# ADE7753.net
KiCad netlist of a schematic drawn in Altium Designer
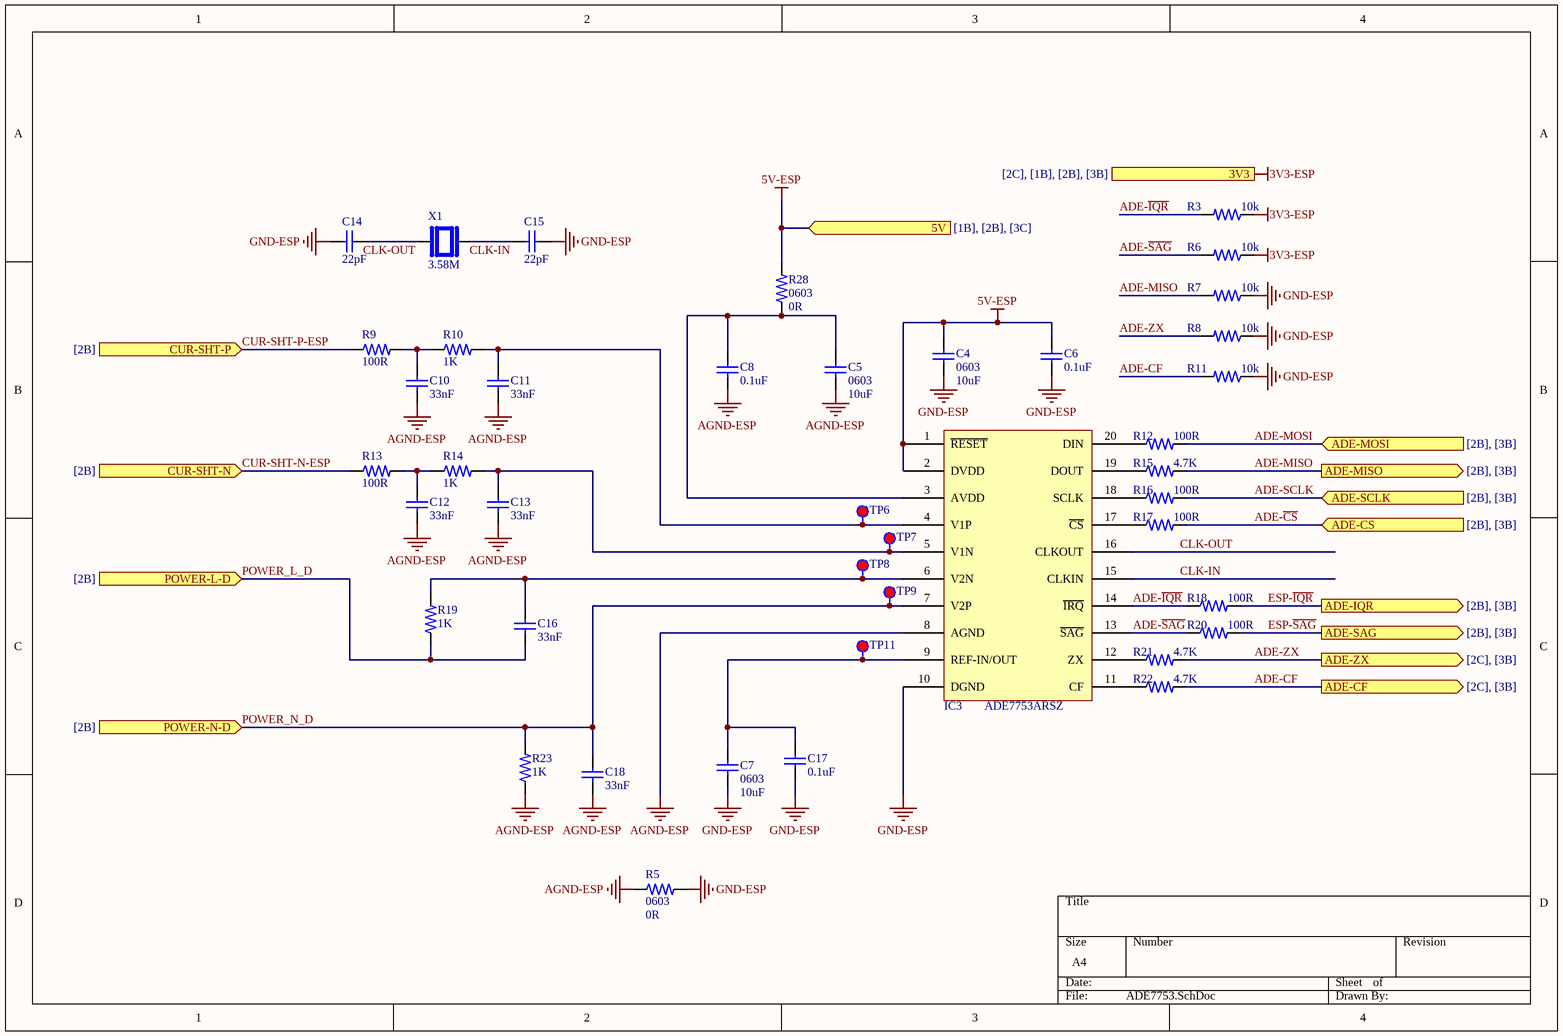
[diagram p0: ADE7753.SchDoc]

(export (version "E")
  (design (tool "Eeschema 10.0.6"))
  (components
    (comp (ref "C4")
      (value "10uF")
      (footprint "SMD-CAP-0603-YAGEO")
      (description "Multilayer Ceramic Capacitor, 10 uF, 25 V, ï¿½ 20%, X5R, 0603 [1608 Metric]")
      (fields
        (field (name "MANUFACTURER") "Yageo")
        (field (name "MANUFACTURER PART NUMBER") "CC0603MRX5R8BB106")
        (field (name "PACKAGE") "0603")
        (field (name "DESIGNER") "TVBac")
      )
      (libsource (lib "Capacitors") (part "CAP; 10uF; 25V; SMD; 0603; CC0603MRX5R8BB106"))
    )
    (comp (ref "C5")
      (value "10uF")
      (footprint "SMD-CAP-0603-YAGEO")
      (description "Multilayer Ceramic Capacitor, 10 uF, 25 V, ï¿½ 20%, X5R, 0603 [1608 Metric]")
      (fields
        (field (name "MANUFACTURER") "Yageo")
        (field (name "MANUFACTURER PART NUMBER") "CC0603MRX5R8BB106")
        (field (name "PACKAGE") "0603")
        (field (name "DESIGNER") "TVBac")
      )
      (libsource (lib "Capacitors") (part "CAP; 10uF; 25V; SMD; 0603; CC0603MRX5R8BB106"))
    )
    (comp (ref "C6")
      (value "0.1uF")
      (footprint "SMD-CAP-0603-YAGEO")
      (description "0603 0.1 uF 16 V ±10 % Tolerance X7R SMT Multilayer Ceramic Capacitor")
      (fields
        (field (name "MANUFACTURER") "Yageo")
        (field (name "MANUFACTURER PART NUMBER") "CC0603KRX7R7BB104")
        (field (name "DESIGNER") "TVBac")
      )
      (libsource (lib "Capacitors") (part "CAP; 0.1uF; 16V; 0603; SMD; CC0603KRX7R7BB104"))
    )
    (comp (ref "C7")
      (value "10uF")
      (footprint "SMD-CAP-0603-YAGEO")
      (description "Multilayer Ceramic Capacitor, 10 uF, 25 V, ï¿½ 20%, X5R, 0603 [1608 Metric]")
      (fields
        (field (name "MANUFACTURER") "Yageo")
        (field (name "MANUFACTURER PART NUMBER") "CC0603MRX5R8BB106")
        (field (name "PACKAGE") "0603")
        (field (name "DESIGNER") "TVBac")
      )
      (libsource (lib "Capacitors") (part "CAP; 10uF; 25V; SMD; 0603; CC0603MRX5R8BB106"))
    )
    (comp (ref "C8")
      (value "0.1uF")
      (footprint "SMD-CAP-0603-YAGEO")
      (description "0603 0.1 uF 16 V ±10 % Tolerance X7R SMT Multilayer Ceramic Capacitor")
      (fields
        (field (name "MANUFACTURER") "Yageo")
        (field (name "MANUFACTURER PART NUMBER") "CC0603KRX7R7BB104")
        (field (name "DESIGNER") "TVBac")
      )
      (libsource (lib "Capacitors") (part "CAP; 0.1uF; 16V; 0603; SMD; CC0603KRX7R7BB104"))
    )
    (comp (ref "C10")
      (value "33nF")
      (footprint "SMD-CAP-0603-KEMET")
      (description "Multilayer Ceramic Capacitors MLCC - SMD/SMT 16V 0.033uF X7R 0603 5%")
      (fields
        (field (name "MANUFACTURER") "KEMET")
        (field (name "MANUFACTURER PART NUMBER") "C0603C333J4REC7411")
        (field (name "DESIGNER") "TVBac")
      )
      (libsource (lib "Capacitors") (part "CAP; 0.033uF; 33nF; 0603; 16V; C0603C333J4REC7411"))
    )
    (comp (ref "C11")
      (value "33nF")
      (footprint "SMD-CAP-0603-KEMET")
      (description "Multilayer Ceramic Capacitors MLCC - SMD/SMT 16V 0.033uF X7R 0603 5%")
      (fields
        (field (name "MANUFACTURER") "KEMET")
        (field (name "MANUFACTURER PART NUMBER") "C0603C333J4REC7411")
        (field (name "DESIGNER") "TVBac")
      )
      (libsource (lib "Capacitors") (part "CAP; 0.033uF; 33nF; 0603; 16V; C0603C333J4REC7411"))
    )
    (comp (ref "C12")
      (value "33nF")
      (footprint "SMD-CAP-0603-KEMET")
      (description "Multilayer Ceramic Capacitors MLCC - SMD/SMT 16V 0.033uF X7R 0603 5%")
      (fields
        (field (name "MANUFACTURER") "KEMET")
        (field (name "MANUFACTURER PART NUMBER") "C0603C333J4REC7411")
        (field (name "DESIGNER") "TVBac")
      )
      (libsource (lib "Capacitors") (part "CAP; 0.033uF; 33nF; 0603; 16V; C0603C333J4REC7411"))
    )
    (comp (ref "C13")
      (value "33nF")
      (footprint "SMD-CAP-0603-KEMET")
      (description "Multilayer Ceramic Capacitors MLCC - SMD/SMT 16V 0.033uF X7R 0603 5%")
      (fields
        (field (name "MANUFACTURER") "KEMET")
        (field (name "MANUFACTURER PART NUMBER") "C0603C333J4REC7411")
        (field (name "DESIGNER") "TVBac")
      )
      (libsource (lib "Capacitors") (part "CAP; 0.033uF; 33nF; 0603; 16V; C0603C333J4REC7411"))
    )
    (comp (ref "C14")
      (value "22pF")
      (footprint "SMD-CAP-0603-YAGEO")
      (description "Multilayer Ceramic Capacitor, 22 pF, 50 V, ï¿½ 1%, C0G (NP0), 0603 [1608 Metric]")
      (fields
        (field (name "MANUFACTURER") "Yageo")
        (field (name "MANUFACTURER PART NUMBER") "CC0603FRNPO9BN220")
        (field (name "DESIGNER") "TVBac")
      )
      (libsource (lib "Capacitors") (part "CAP; 22pF; 50V; SMD; CC0603FRNPO9BN220"))
    )
    (comp (ref "C15")
      (value "22pF")
      (footprint "SMD-CAP-0603-YAGEO")
      (description "Multilayer Ceramic Capacitor, 22 pF, 50 V, ï¿½ 1%, C0G (NP0), 0603 [1608 Metric]")
      (fields
        (field (name "MANUFACTURER") "Yageo")
        (field (name "MANUFACTURER PART NUMBER") "CC0603FRNPO9BN220")
        (field (name "DESIGNER") "TVBac")
      )
      (libsource (lib "Capacitors") (part "CAP; 22pF; 50V; SMD; CC0603FRNPO9BN220"))
    )
    (comp (ref "C16")
      (value "33nF")
      (footprint "SMD-CAP-0603-KEMET")
      (description "Multilayer Ceramic Capacitors MLCC - SMD/SMT 16V 0.033uF X7R 0603 5%")
      (fields
        (field (name "MANUFACTURER") "KEMET")
        (field (name "MANUFACTURER PART NUMBER") "C0603C333J4REC7411")
        (field (name "DESIGNER") "TVBac")
      )
      (libsource (lib "Capacitors") (part "CAP; 0.033uF; 33nF; 0603; 16V; C0603C333J4REC7411"))
    )
    (comp (ref "C17")
      (value "0.1uF")
      (footprint "SMD-CAP-0603-YAGEO")
      (description "0603 0.1 uF 16 V ±10 % Tolerance X7R SMT Multilayer Ceramic Capacitor")
      (fields
        (field (name "MANUFACTURER") "Yageo")
        (field (name "MANUFACTURER PART NUMBER") "CC0603KRX7R7BB104")
        (field (name "DESIGNER") "TVBac")
      )
      (libsource (lib "Capacitors") (part "CAP; 0.1uF; 16V; 0603; SMD; CC0603KRX7R7BB104"))
    )
    (comp (ref "C18")
      (value "33nF")
      (footprint "SMD-CAP-0603-KEMET")
      (description "Multilayer Ceramic Capacitors MLCC - SMD/SMT 16V 0.033uF X7R 0603 5%")
      (fields
        (field (name "MANUFACTURER") "KEMET")
        (field (name "MANUFACTURER PART NUMBER") "C0603C333J4REC7411")
        (field (name "DESIGNER") "TVBac")
      )
      (libsource (lib "Capacitors") (part "CAP; 0.033uF; 33nF; 0603; 16V; C0603C333J4REC7411"))
    )
    (comp (ref "IC3")
      (value "Single Phase Meter IC 20-SSOP")
      (footprint "SSOP-20-ADI")
      (description "Single Phase Multifunction Metering IC 20-Pin SSOP Tube")
      (fields
        (field (name "MANUFACTURER") "Analog Devices")
        (field (name "MANUFACTURER PART NUMBER") "ADE7753ARSZ")
        (field (name "DESIGNER") "TVBac")
      )
      (libsource (lib "IC") (part "ADE7753ARSZ"))
    )
    (comp (ref "R3")
      (value "10k")
      (footprint "SMD-RES-0603-SEI")
      (description "SMD Chip Resistor, 10 kOhm, ± 1%, 250 mW, 0603 [1608 Metric], Thick Film, Anti-Surge")
      (fields
        (field (name "MANUFACTURER") "Rohm")
        (field (name "MANUFACTURER PART NUMBER") "ESR03EZPF1002")
        (field (name "DESIGNER") "TVBac")
      )
      (libsource (lib "Resistors") (part "RES; 10K; 0603; SMD; ESR03EZPF1002"))
    )
    (comp (ref "R5")
      (value "0R")
      (footprint "SMD-RES-0603-SEI")
      (description "Res Thick 0603 0 Ohm Jumper 1/10W 100Ppm/ C Smd Rohs Compliant: Yes")
      (fields
        (field (name "MANUFACTURER") "Stackpole Electronics")
        (field (name "MANUFACTURER PART NUMBER") "RMCF0603ZT0R00")
        (field (name "PACKAGE") "0603")
        (field (name "DESIGNER") "TVBac")
      )
      (libsource (lib "Resistors") (part "RES; 0R; 0603; SMD;  RMCF0603ZT0R00"))
    )
    (comp (ref "R6")
      (value "10k")
      (footprint "SMD-RES-0603-SEI")
      (description "SMD Chip Resistor, 10 kOhm, ± 1%, 250 mW, 0603 [1608 Metric], Thick Film, Anti-Surge")
      (fields
        (field (name "MANUFACTURER") "Rohm")
        (field (name "MANUFACTURER PART NUMBER") "ESR03EZPF1002")
        (field (name "DESIGNER") "TVBac")
      )
      (libsource (lib "Resistors") (part "RES; 10K; 0603; SMD; ESR03EZPF1002"))
    )
    (comp (ref "R7")
      (value "10k")
      (footprint "SMD-RES-0603-SEI")
      (description "SMD Chip Resistor, 10 kOhm, ± 1%, 250 mW, 0603 [1608 Metric], Thick Film, Anti-Surge")
      (fields
        (field (name "MANUFACTURER") "Rohm")
        (field (name "MANUFACTURER PART NUMBER") "ESR03EZPF1002")
        (field (name "DESIGNER") "TVBac")
      )
      (libsource (lib "Resistors") (part "RES; 10K; 0603; SMD; ESR03EZPF1002"))
    )
    (comp (ref "R8")
      (value "10k")
      (footprint "SMD-RES-0603-SEI")
      (description "SMD Chip Resistor, 10 kOhm, ± 1%, 250 mW, 0603 [1608 Metric], Thick Film, Anti-Surge")
      (fields
        (field (name "MANUFACTURER") "Rohm")
        (field (name "MANUFACTURER PART NUMBER") "ESR03EZPF1002")
        (field (name "DESIGNER") "TVBac")
      )
      (libsource (lib "Resistors") (part "RES; 10K; 0603; SMD; ESR03EZPF1002"))
    )
    (comp (ref "R9")
      (value "100R")
      (footprint "SMD-RES-0603-RS")
      (description "Res Thick Film 0603 100 Ohm 1% 0.1W(1/10W) ±100ppm/C Pad SMD T/R Automotive AEC-Q200")
      (fields
        (field (name "MANUFACTURER") "Rohm")
        (field (name "MANUFACTURER PART NUMBER") "KTR03EZPF1000")
        (field (name "DESIGNER") "TVBac")
      )
      (libsource (lib "Resistors") (part "RES; 100R; 0603; SMD; KTR03EZPF1000"))
    )
    (comp (ref "R10")
      (value "1K")
      (footprint "SMD-RES-0603-SEI")
      (description "SMD Chip Resistor, 1 kOhm, ± 1%, 250 mW, 0603 [1608 Metric], Thick Film, Anti-Surge")
      (fields
        (field (name "MANUFACTURER") "Rohm")
        (field (name "MANUFACTURER PART NUMBER") "ESR03EZPF1001")
        (field (name "DESIGNER") "TVBac")
      )
      (libsource (lib "Resistors") (part "RES; 1K; 0603; SMD; ESR03EZPF1001"))
    )
    (comp (ref "R11")
      (value "10k")
      (footprint "SMD-RES-0603-SEI")
      (description "SMD Chip Resistor, 10 kOhm, ± 1%, 250 mW, 0603 [1608 Metric], Thick Film, Anti-Surge")
      (fields
        (field (name "MANUFACTURER") "Rohm")
        (field (name "MANUFACTURER PART NUMBER") "ESR03EZPF1002")
        (field (name "DESIGNER") "TVBac")
      )
      (libsource (lib "Resistors") (part "RES; 10K; 0603; SMD; ESR03EZPF1002"))
    )
    (comp (ref "R12")
      (value "100R")
      (footprint "SMD-RES-0603-RS")
      (description "Res Thick Film 0603 100 Ohm 1% 0.1W(1/10W) ±100ppm/C Pad SMD T/R Automotive AEC-Q200")
      (fields
        (field (name "MANUFACTURER") "Rohm")
        (field (name "MANUFACTURER PART NUMBER") "KTR03EZPF1000")
        (field (name "DESIGNER") "TVBac")
      )
      (libsource (lib "Resistors") (part "RES; 100R; 0603; SMD; KTR03EZPF1000"))
    )
    (comp (ref "R13")
      (value "100R")
      (footprint "SMD-RES-0603-RS")
      (description "Res Thick Film 0603 100 Ohm 1% 0.1W(1/10W) ±100ppm/C Pad SMD T/R Automotive AEC-Q200")
      (fields
        (field (name "MANUFACTURER") "Rohm")
        (field (name "MANUFACTURER PART NUMBER") "KTR03EZPF1000")
        (field (name "DESIGNER") "TVBac")
      )
      (libsource (lib "Resistors") (part "RES; 100R; 0603; SMD; KTR03EZPF1000"))
    )
    (comp (ref "R14")
      (value "1K")
      (footprint "SMD-RES-0603-SEI")
      (description "SMD Chip Resistor, 1 kOhm, ± 1%, 250 mW, 0603 [1608 Metric], Thick Film, Anti-Surge")
      (fields
        (field (name "MANUFACTURER") "Rohm")
        (field (name "MANUFACTURER PART NUMBER") "ESR03EZPF1001")
        (field (name "DESIGNER") "TVBac")
      )
      (libsource (lib "Resistors") (part "RES; 1K; 0603; SMD; ESR03EZPF1001"))
    )
    (comp (ref "R15")
      (value "4.7K")
      (footprint "SMD-RES-0603-RS")
      (description "Res Anti-Sulfured Thick Film 0603 4.7k Ohm 1% 1/10W ±100ppm/°C Molded Paper T/R")
      (fields
        (field (name "MANUFACTURER") "Rohm")
        (field (name "MANUFACTURER PART NUMBER") "SFR03EZPF4701")
        (field (name "DESIGNER") "TVBac")
      )
      (libsource (lib "Resistors") (part "RES; 4.7K; 0603; SMD; SFR03EZPF4701"))
    )
    (comp (ref "R16")
      (value "100R")
      (footprint "SMD-RES-0603-RS")
      (description "Res Thick Film 0603 100 Ohm 1% 0.1W(1/10W) ±100ppm/C Pad SMD T/R Automotive AEC-Q200")
      (fields
        (field (name "MANUFACTURER") "Rohm")
        (field (name "MANUFACTURER PART NUMBER") "KTR03EZPF1000")
        (field (name "DESIGNER") "TVBac")
      )
      (libsource (lib "Resistors") (part "RES; 100R; 0603; SMD; KTR03EZPF1000"))
    )
    (comp (ref "R17")
      (value "100R")
      (footprint "SMD-RES-0603-RS")
      (description "Res Thick Film 0603 100 Ohm 1% 0.1W(1/10W) ±100ppm/C Pad SMD T/R Automotive AEC-Q200")
      (fields
        (field (name "MANUFACTURER") "Rohm")
        (field (name "MANUFACTURER PART NUMBER") "KTR03EZPF1000")
        (field (name "DESIGNER") "TVBac")
      )
      (libsource (lib "Resistors") (part "RES; 100R; 0603; SMD; KTR03EZPF1000"))
    )
    (comp (ref "R18")
      (value "100R")
      (footprint "SMD-RES-0603-RS")
      (description "Res Thick Film 0603 100 Ohm 1% 0.1W(1/10W) ±100ppm/C Pad SMD T/R Automotive AEC-Q200")
      (fields
        (field (name "MANUFACTURER") "Rohm")
        (field (name "MANUFACTURER PART NUMBER") "KTR03EZPF1000")
        (field (name "DESIGNER") "TVBac")
      )
      (libsource (lib "Resistors") (part "RES; 100R; 0603; SMD; KTR03EZPF1000"))
    )
    (comp (ref "R19")
      (value "1K")
      (footprint "SMD-RES-0603-SEI")
      (description "SMD Chip Resistor, 1 kOhm, ± 1%, 250 mW, 0603 [1608 Metric], Thick Film, Anti-Surge")
      (fields
        (field (name "MANUFACTURER") "Rohm")
        (field (name "MANUFACTURER PART NUMBER") "ESR03EZPF1001")
        (field (name "DESIGNER") "TVBac")
      )
      (libsource (lib "Resistors") (part "RES; 1K; 0603; SMD; ESR03EZPF1001"))
    )
    (comp (ref "R20")
      (value "100R")
      (footprint "SMD-RES-0603-RS")
      (description "Res Thick Film 0603 100 Ohm 1% 0.1W(1/10W) ±100ppm/C Pad SMD T/R Automotive AEC-Q200")
      (fields
        (field (name "MANUFACTURER") "Rohm")
        (field (name "MANUFACTURER PART NUMBER") "KTR03EZPF1000")
        (field (name "DESIGNER") "TVBac")
      )
      (libsource (lib "Resistors") (part "RES; 100R; 0603; SMD; KTR03EZPF1000"))
    )
    (comp (ref "R21")
      (value "4.7K")
      (footprint "SMD-RES-0603-RS")
      (description "Res Anti-Sulfured Thick Film 0603 4.7k Ohm 1% 1/10W ±100ppm/°C Molded Paper T/R")
      (fields
        (field (name "MANUFACTURER") "Rohm")
        (field (name "MANUFACTURER PART NUMBER") "SFR03EZPF4701")
        (field (name "DESIGNER") "TVBac")
      )
      (libsource (lib "Resistors") (part "RES; 4.7K; 0603; SMD; SFR03EZPF4701"))
    )
    (comp (ref "R22")
      (value "4.7K")
      (footprint "SMD-RES-0603-RS")
      (description "Res Anti-Sulfured Thick Film 0603 4.7k Ohm 1% 1/10W ±100ppm/°C Molded Paper T/R")
      (fields
        (field (name "MANUFACTURER") "Rohm")
        (field (name "MANUFACTURER PART NUMBER") "SFR03EZPF4701")
        (field (name "DESIGNER") "TVBac")
      )
      (libsource (lib "Resistors") (part "RES; 4.7K; 0603; SMD; SFR03EZPF4701"))
    )
    (comp (ref "R23")
      (value "1K")
      (footprint "SMD-RES-0603-SEI")
      (description "SMD Chip Resistor, 1 kOhm, ± 1%, 250 mW, 0603 [1608 Metric], Thick Film, Anti-Surge")
      (fields
        (field (name "MANUFACTURER") "Rohm")
        (field (name "MANUFACTURER PART NUMBER") "ESR03EZPF1001")
        (field (name "DESIGNER") "TVBac")
      )
      (libsource (lib "Resistors") (part "RES; 1K; 0603; SMD; ESR03EZPF1001"))
    )
    (comp (ref "R28")
      (value "0R")
      (footprint "SMD-RES-0603-SEI")
      (description "Res Thick 0603 0 Ohm Jumper 1/10W 100Ppm/ C Smd Rohs Compliant: Yes")
      (fields
        (field (name "MANUFACTURER") "Stackpole Electronics")
        (field (name "MANUFACTURER PART NUMBER") "RMCF0603ZT0R00")
        (field (name "PACKAGE") "0603")
        (field (name "DESIGNER") "TVBac")
      )
      (libsource (lib "Resistors") (part "RES; 0R; 0603; SMD;  RMCF0603ZT0R00"))
    )
    (comp (ref "TP6")
      (value "Test Point")
      (footprint "TEST_POINT")
      (libsource (lib "Socket") (part "TEST_POINT"))
    )
    (comp (ref "TP7")
      (value "Test Point")
      (footprint "TEST_POINT")
      (libsource (lib "Socket") (part "TEST_POINT"))
    )
    (comp (ref "TP8")
      (value "Test Point")
      (footprint "TEST_POINT")
      (libsource (lib "Socket") (part "TEST_POINT"))
    )
    (comp (ref "TP9")
      (value "Test Point")
      (footprint "TEST_POINT")
      (libsource (lib "Socket") (part "TEST_POINT"))
    )
    (comp (ref "TP11")
      (value "Test Point")
      (footprint "TEST_POINT")
      (libsource (lib "Socket") (part "TEST_POINT"))
    )
    (comp (ref "X1")
      (value "3.58M")
      (footprint "SMD-HC-49/US-ALLC")
      (description "Crystal 3.579545MHz ±20ppm (Tol) ±50ppm (Stability) 18pF FUND 180Ohm 2-Pin HC-49/US SMD T/R")
      (fields
        (field (name "MANUFACTURER") "Abracon")
        (field (name "MANUFACTURER PART NUMBER") "ABLS-3.579545MHZ-B2-T")
        (field (name "DESIGNER") "TVBac")
      )
      (libsource (lib "Oscillators") (part "OSC; 3.58M; 3.579545M; ABLS-3.579545MHZ-B2-T"))
    )
  )
  (nets
    (net (code "1") (name "/ADE-CF") (class "Default")
      (node (ref "R11") (pin "2") (pinfunction "2_2") (pintype "passive"))
      (node (ref "R22") (pin "2") (pinfunction "2_2") (pintype "passive"))
    )
    (net (code "2") (name "/ADE-MISO") (class "Default")
      (node (ref "R15") (pin "2") (pinfunction "2_2") (pintype "passive"))
      (node (ref "R7") (pin "2") (pinfunction "2_2") (pintype "passive"))
    )
    (net (code "3") (name "/ADE-MOSI") (class "Default")
      (node (ref "R12") (pin "2") (pinfunction "2_2") (pintype "passive"))
    )
    (net (code "4") (name "/ADE-SCLK") (class "Default")
      (node (ref "R16") (pin "2") (pinfunction "2_2") (pintype "passive"))
    )
    (net (code "5") (name "/ADE-ZX") (class "Default")
      (node (ref "R21") (pin "2") (pinfunction "2_2") (pintype "passive"))
      (node (ref "R8") (pin "2") (pinfunction "2_2") (pintype "passive"))
    )
    (net (code "6") (name "/ADE-~{CS}") (class "Default")
      (node (ref "R17") (pin "2") (pinfunction "2_2") (pintype "passive"))
    )
    (net (code "7") (name "/ADE-~{IQR}") (class "Default")
      (node (ref "IC3") (pin "14") (pinfunction "~{IRQ}_14") (pintype "passive"))
      (node (ref "R18") (pin "1") (pinfunction "1_1") (pintype "passive"))
      (node (ref "R3") (pin "2") (pinfunction "2_2") (pintype "passive"))
    )
    (net (code "8") (name "/ADE-~{SAG}") (class "Default")
      (node (ref "IC3") (pin "13") (pinfunction "~{SAG}_13") (pintype "passive"))
      (node (ref "R20") (pin "1") (pinfunction "1_1") (pintype "passive"))
      (node (ref "R6") (pin "2") (pinfunction "2_2") (pintype "passive"))
    )
    (net (code "9") (name "/CLK-IN") (class "Default")
      (node (ref "C15") (pin "1") (pinfunction "1_1") (pintype "passive"))
      (node (ref "IC3") (pin "15") (pinfunction "CLKIN_15") (pintype "passive"))
      (node (ref "X1") (pin "2") (pinfunction "2_2") (pintype "passive"))
    )
    (net (code "10") (name "/CLK-OUT") (class "Default")
      (node (ref "C14") (pin "2") (pinfunction "2_2") (pintype "passive"))
      (node (ref "IC3") (pin "16") (pinfunction "CLKOUT_16") (pintype "passive"))
      (node (ref "X1") (pin "1") (pinfunction "1_1") (pintype "passive"))
    )
    (net (code "11") (name "/CUR-SHT-N-ESP") (class "Default")
      (node (ref "R13") (pin "1") (pinfunction "1_1") (pintype "passive"))
    )
    (net (code "12") (name "/CUR-SHT-P-ESP") (class "Default")
      (node (ref "R9") (pin "1") (pinfunction "1_1") (pintype "passive"))
    )
    (net (code "13") (name "/ESP-~{IQR}") (class "Default")
      (node (ref "R18") (pin "2") (pinfunction "2_2") (pintype "passive"))
    )
    (net (code "14") (name "/ESP-~{SAG}") (class "Default")
      (node (ref "R20") (pin "2") (pinfunction "2_2") (pintype "passive"))
    )
    (net (code "15") (name "/POWER_L_D") (class "Default")
      (node (ref "C16") (pin "1") (pinfunction "1_1") (pintype "passive"))
      (node (ref "R19") (pin "1") (pinfunction "1_1") (pintype "passive"))
    )
    (net (code "16") (name "/POWER_N_D") (class "Default")
      (node (ref "C18") (pin "2") (pinfunction "2_2") (pintype "passive"))
      (node (ref "IC3") (pin "7") (pinfunction "V2P_7") (pintype "passive"))
      (node (ref "R23") (pin "2") (pinfunction "2_2") (pintype "passive"))
      (node (ref "TP9") (pin "1") (pinfunction "1_1") (pintype "passive"))
    )
    (net (code "17") (name "3V3-ESP") (class "Default")
      (node (ref "R3") (pin "1") (pinfunction "1_1") (pintype "passive"))
      (node (ref "R6") (pin "1") (pinfunction "1_1") (pintype "passive"))
    )
    (net (code "18") (name "5V-ESP") (class "Default")
      (node (ref "C4") (pin "2") (pinfunction "2_2") (pintype "passive"))
      (node (ref "C6") (pin "2") (pinfunction "2_2") (pintype "passive"))
      (node (ref "IC3") (pin "1") (pinfunction "~{RESET}_1") (pintype "passive"))
      (node (ref "IC3") (pin "2") (pinfunction "DVDD_2") (pintype "passive"))
      (node (ref "R28") (pin "2") (pinfunction "2_2") (pintype "passive"))
    )
    (net (code "19") (name "AGND-ESP") (class "Default")
      (node (ref "C10") (pin "1") (pinfunction "1_1") (pintype "passive"))
      (node (ref "C11") (pin "1") (pinfunction "1_1") (pintype "passive"))
      (node (ref "C12") (pin "1") (pinfunction "1_1") (pintype "passive"))
      (node (ref "C13") (pin "1") (pinfunction "1_1") (pintype "passive"))
      (node (ref "C18") (pin "1") (pinfunction "1_1") (pintype "passive"))
      (node (ref "C5") (pin "1") (pinfunction "1_1") (pintype "passive"))
      (node (ref "C8") (pin "1") (pinfunction "1_1") (pintype "passive"))
      (node (ref "IC3") (pin "8") (pinfunction "AGND_8") (pintype "passive"))
      (node (ref "R23") (pin "1") (pinfunction "1_1") (pintype "passive"))
      (node (ref "R5") (pin "1") (pinfunction "1_1") (pintype "passive"))
    )
    (net (code "20") (name "GND-ESP") (class "Default")
      (node (ref "C14") (pin "1") (pinfunction "1_1") (pintype "passive"))
      (node (ref "C15") (pin "2") (pinfunction "2_2") (pintype "passive"))
      (node (ref "C17") (pin "1") (pinfunction "1_1") (pintype "passive"))
      (node (ref "C4") (pin "1") (pinfunction "1_1") (pintype "passive"))
      (node (ref "C6") (pin "1") (pinfunction "1_1") (pintype "passive"))
      (node (ref "C7") (pin "1") (pinfunction "1_1") (pintype "passive"))
      (node (ref "IC3") (pin "10") (pinfunction "DGND_10") (pintype "passive"))
      (node (ref "R11") (pin "1") (pinfunction "1_1") (pintype "passive"))
      (node (ref "R5") (pin "2") (pinfunction "2_2") (pintype "passive"))
      (node (ref "R7") (pin "1") (pinfunction "1_1") (pintype "passive"))
      (node (ref "R8") (pin "1") (pinfunction "1_1") (pintype "passive"))
    )
    (net (code "21") (name "Net-(C10-Pad2)") (class "Default")
      (node (ref "C10") (pin "2") (pinfunction "2_2") (pintype "passive"))
      (node (ref "R10") (pin "1") (pinfunction "1_1") (pintype "passive"))
      (node (ref "R9") (pin "2") (pinfunction "2_2") (pintype "passive"))
    )
    (net (code "22") (name "Net-(C12-Pad2)") (class "Default")
      (node (ref "C12") (pin "2") (pinfunction "2_2") (pintype "passive"))
      (node (ref "R13") (pin "2") (pinfunction "2_2") (pintype "passive"))
      (node (ref "R14") (pin "1") (pinfunction "1_1") (pintype "passive"))
    )
    (net (code "23") (name "Net-(IC3-AVDD)") (class "Default")
      (node (ref "C5") (pin "2") (pinfunction "2_2") (pintype "passive"))
      (node (ref "C8") (pin "2") (pinfunction "2_2") (pintype "passive"))
      (node (ref "IC3") (pin "3") (pinfunction "AVDD_3") (pintype "passive"))
      (node (ref "R28") (pin "1") (pinfunction "1_1") (pintype "passive"))
    )
    (net (code "24") (name "Net-(IC3-CF)") (class "Default")
      (node (ref "IC3") (pin "11") (pinfunction "CF_11") (pintype "passive"))
      (node (ref "R22") (pin "1") (pinfunction "1_1") (pintype "passive"))
    )
    (net (code "25") (name "Net-(IC3-DIN)") (class "Default")
      (node (ref "IC3") (pin "20") (pinfunction "DIN_20") (pintype "passive"))
      (node (ref "R12") (pin "1") (pinfunction "1_1") (pintype "passive"))
    )
    (net (code "26") (name "Net-(IC3-DOUT)") (class "Default")
      (node (ref "IC3") (pin "19") (pinfunction "DOUT_19") (pintype "passive"))
      (node (ref "R15") (pin "1") (pinfunction "1_1") (pintype "passive"))
    )
    (net (code "27") (name "Net-(IC3-REF-IN{slash}OUT)") (class "Default")
      (node (ref "C17") (pin "2") (pinfunction "2_2") (pintype "passive"))
      (node (ref "C7") (pin "2") (pinfunction "2_2") (pintype "passive"))
      (node (ref "IC3") (pin "9") (pinfunction "REF-IN/OUT_9") (pintype "passive"))
      (node (ref "TP11") (pin "1") (pinfunction "1_1") (pintype "passive"))
    )
    (net (code "28") (name "Net-(IC3-SCLK)") (class "Default")
      (node (ref "IC3") (pin "18") (pinfunction "SCLK_18") (pintype "passive"))
      (node (ref "R16") (pin "1") (pinfunction "1_1") (pintype "passive"))
    )
    (net (code "29") (name "Net-(IC3-V1N)") (class "Default")
      (node (ref "C13") (pin "2") (pinfunction "2_2") (pintype "passive"))
      (node (ref "IC3") (pin "5") (pinfunction "V1N_5") (pintype "passive"))
      (node (ref "R14") (pin "2") (pinfunction "2_2") (pintype "passive"))
      (node (ref "TP7") (pin "1") (pinfunction "1_1") (pintype "passive"))
    )
    (net (code "30") (name "Net-(IC3-V1P)") (class "Default")
      (node (ref "C11") (pin "2") (pinfunction "2_2") (pintype "passive"))
      (node (ref "IC3") (pin "4") (pinfunction "V1P_4") (pintype "passive"))
      (node (ref "R10") (pin "2") (pinfunction "2_2") (pintype "passive"))
      (node (ref "TP6") (pin "1") (pinfunction "1_1") (pintype "passive"))
    )
    (net (code "31") (name "Net-(IC3-V2N)") (class "Default")
      (node (ref "C16") (pin "2") (pinfunction "2_2") (pintype "passive"))
      (node (ref "IC3") (pin "6") (pinfunction "V2N_6") (pintype "passive"))
      (node (ref "R19") (pin "2") (pinfunction "2_2") (pintype "passive"))
      (node (ref "TP8") (pin "1") (pinfunction "1_1") (pintype "passive"))
    )
    (net (code "32") (name "Net-(IC3-ZX)") (class "Default")
      (node (ref "IC3") (pin "12") (pinfunction "ZX_12") (pintype "passive"))
      (node (ref "R21") (pin "1") (pinfunction "1_1") (pintype "passive"))
    )
    (net (code "33") (name "Net-(IC3-~{CS})") (class "Default")
      (node (ref "IC3") (pin "17") (pinfunction "~{CS}_17") (pintype "passive"))
      (node (ref "R17") (pin "1") (pinfunction "1_1") (pintype "passive"))
    )
  )
)
